# MCU_and_POWER.net
KiCad netlist of a schematic drawn in Altium Designer
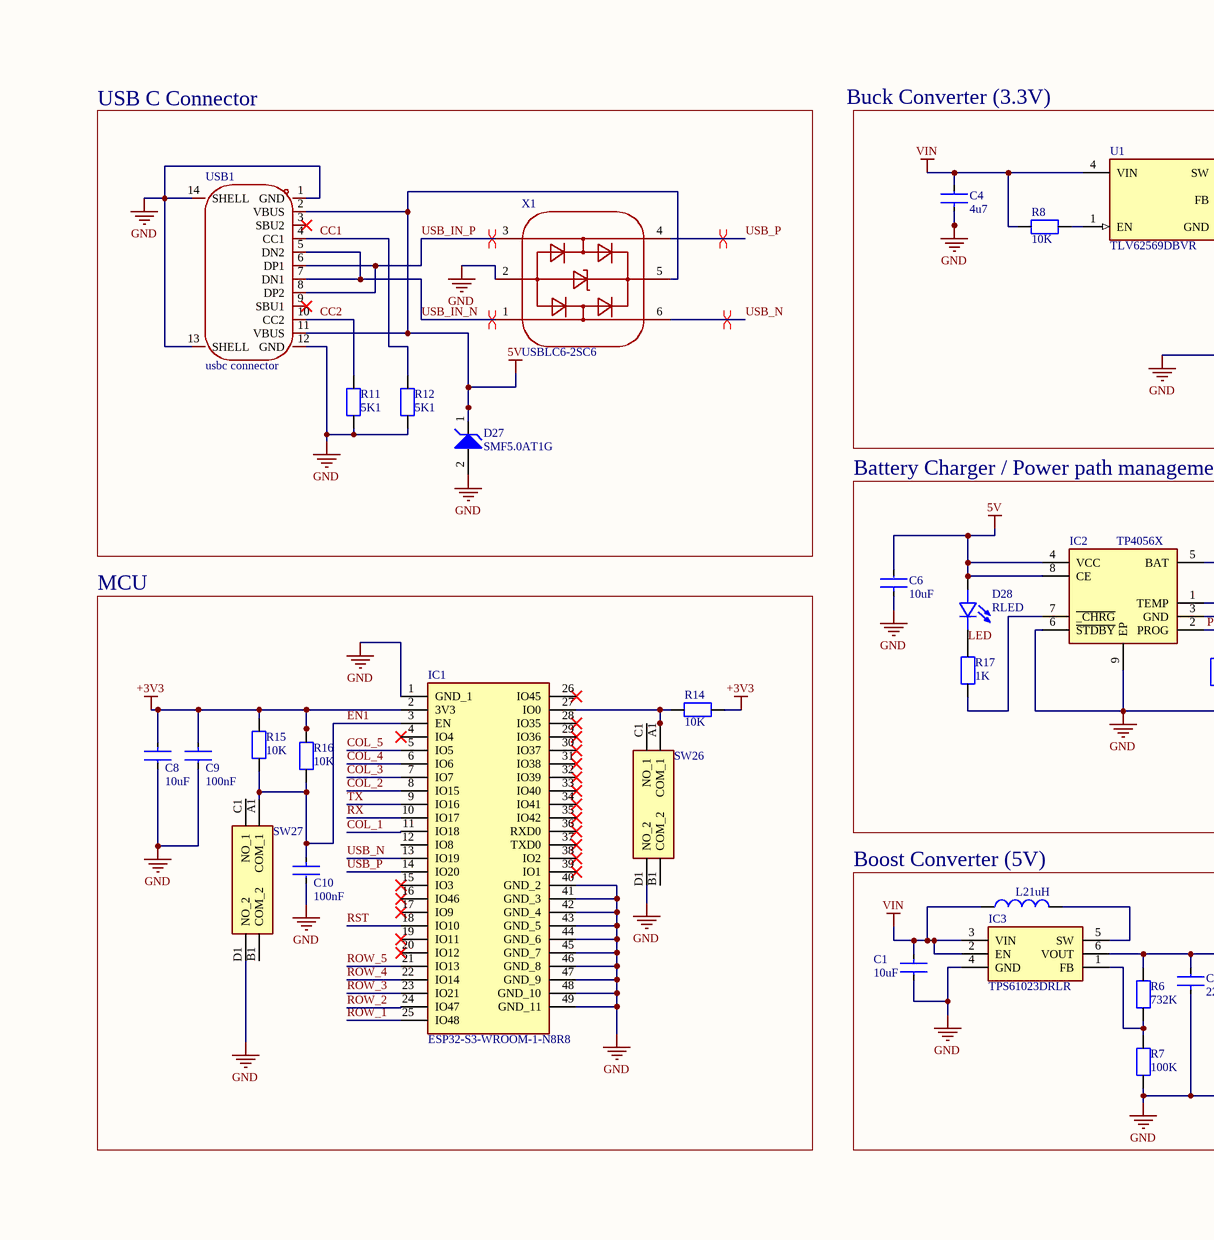
[diagram p0: MCU and POWER.SchDoc, left]
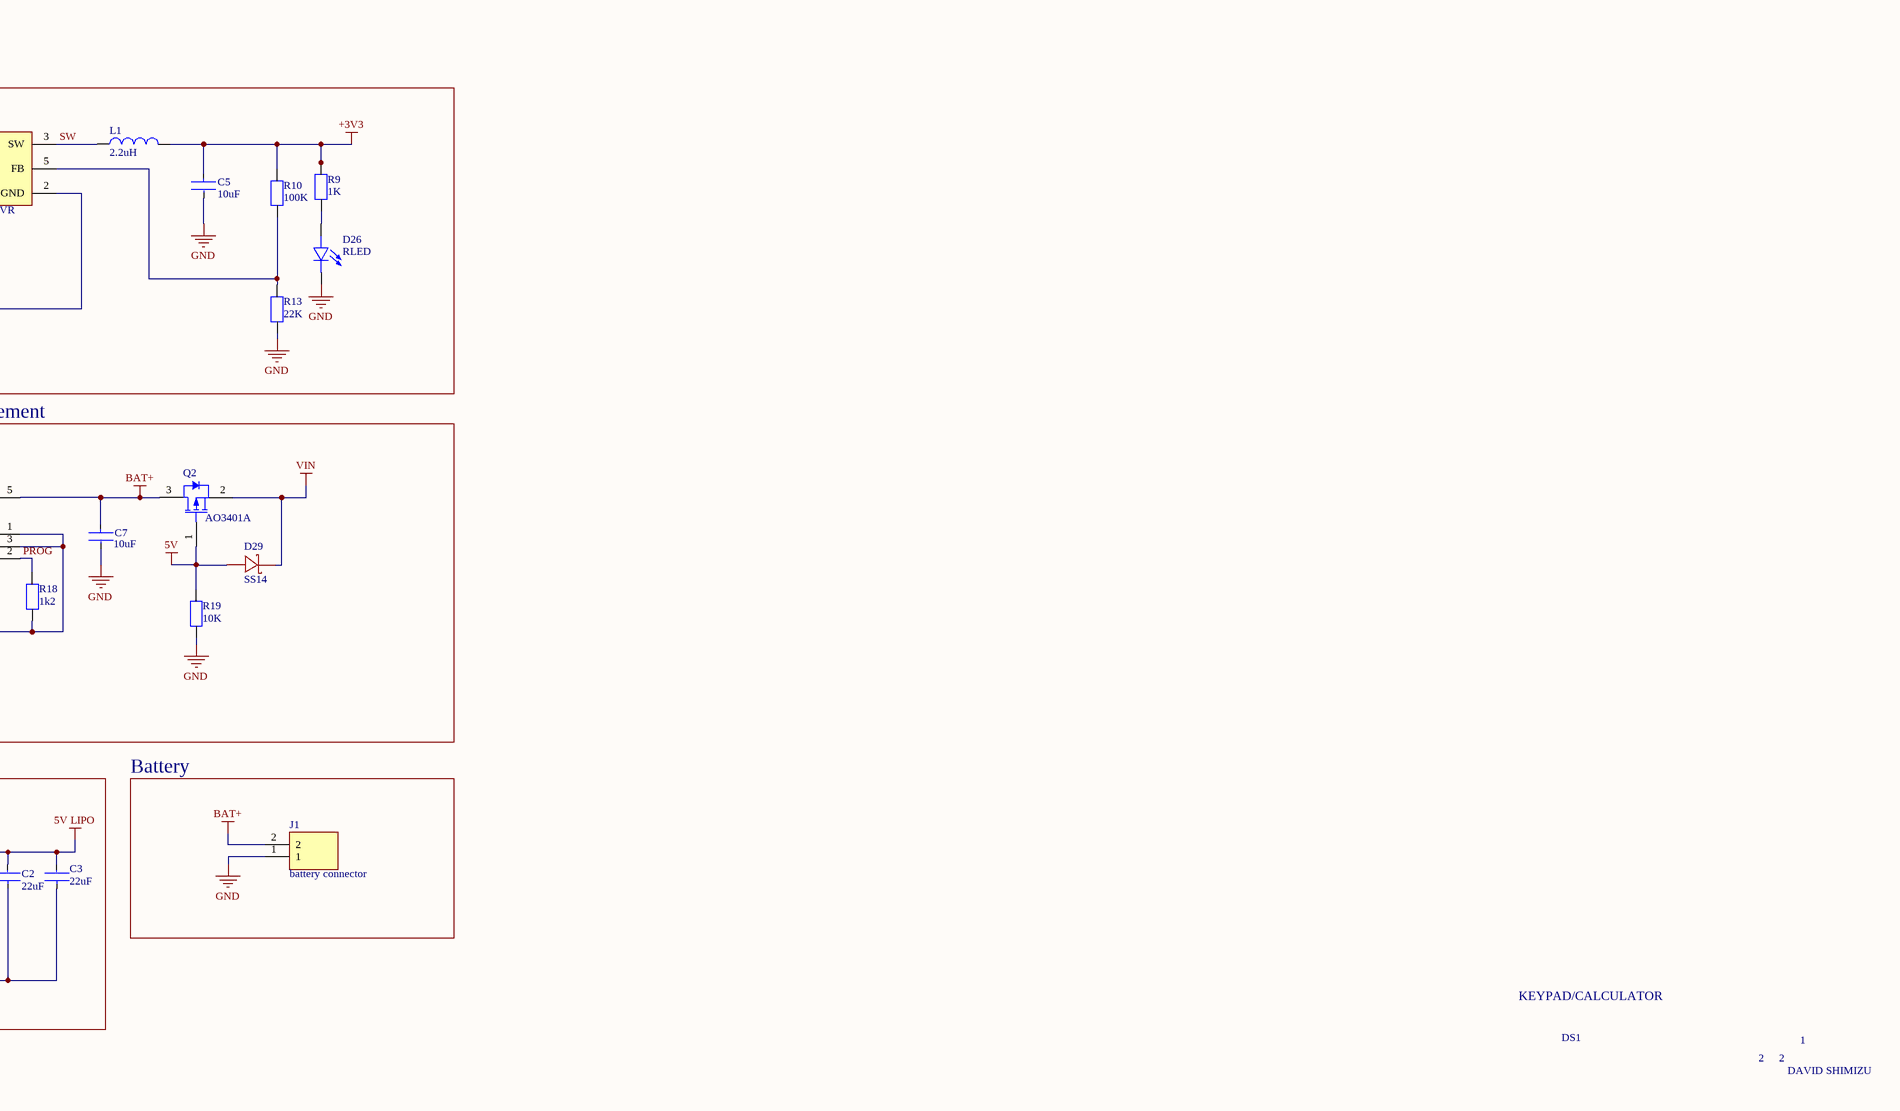
[diagram p1: MCU and POWER.SchDoc, right]

(export (version "E")
  (design (tool "Eeschema 10.0.6"))
  (components
    (comp (ref "C1")
      (value "10uF")
      (footprint "0402 capacitor")
      (description "0402 smd capacitor")
      (libsource (lib "schematiclibrary") (part "0402 capacitor"))
    )
    (comp (ref "C2")
      (value "22uF")
      (footprint "0402 capacitor")
      (description "0402 smd capacitor")
      (libsource (lib "schematiclibrary") (part "0402 capacitor"))
    )
    (comp (ref "C3")
      (value "22uF")
      (footprint "0402 capacitor")
      (description "0402 smd capacitor")
      (libsource (lib "schematiclibrary") (part "0402 capacitor"))
    )
    (comp (ref "C4")
      (value "4u7")
      (footprint "0402 capacitor")
      (description "0402 smd capacitor")
      (libsource (lib "schematiclibrary") (part "0402 capacitor"))
    )
    (comp (ref "C5")
      (value "10uF")
      (footprint "0402 capacitor")
      (description "0402 smd capacitor")
      (libsource (lib "schematiclibrary") (part "0402 capacitor"))
    )
    (comp (ref "C6")
      (value "10uF")
      (footprint "0603 CAPACITOR")
      (libsource (lib "schematiclibrary") (part "0603 capacitor"))
    )
    (comp (ref "C7")
      (value "10uF")
      (footprint "0603 CAPACITOR")
      (libsource (lib "schematiclibrary") (part "0603 capacitor"))
    )
    (comp (ref "C8")
      (value "10uF")
      (footprint "0603 CAPACITOR")
      (libsource (lib "schematiclibrary") (part "0603 capacitor"))
    )
    (comp (ref "C9")
      (value "100nF")
      (footprint "0402 capacitor")
      (description "0402 smd capacitor")
      (libsource (lib "schematiclibrary") (part "0402 capacitor"))
    )
    (comp (ref "C10")
      (value "100nF")
      (footprint "0402 capacitor")
      (description "0402 smd capacitor")
      (libsource (lib "schematiclibrary") (part "0402 capacitor"))
    )
    (comp (ref "D26")
      (value "RLED")
      (footprint "LED_KT-0603R")
      (description "Red 0603 Light Emitting Diodes")
      (fields (field (name "MF") "Hubei KENTO Elec") (field (name "MP") "KT-0603R"))
      (libsource (lib "KT-0603R") (part "KT-0603R"))
    )
    (comp (ref "D27")
      (value "SMF5.0AT1G")
      (footprint "ONSC-SOD-123FL-2-498_V")
      (description "200 W Transient Voltage Suppressor, 2-Pin SOD-123FL, Pb-Free, Tape and Reel")
      (fields (field (name "MANUFACTURER") "On Semiconductor"))
      (libsource (lib "Altium Content Vault") (part "ONSC-K1A2-2"))
    )
    (comp (ref "D28")
      (value "RLED")
      (footprint "LED_KT-0603R")
      (description "Red 0603 Light Emitting Diodes")
      (fields (field (name "MF") "Hubei KENTO Elec") (field (name "MP") "KT-0603R"))
      (libsource (lib "KT-0603R") (part "KT-0603R"))
    )
    (comp (ref "D29")
      (value "SS14")
      (footprint "SMA(DO-214AC)(schottky)")
      (description "40V Independent Type 1A 550mV@1A SMA(DO-214AC) Schottky Diodes ROHS")
      (libsource (lib "schematiclibrary") (part "ss14"))
    )
    (comp (ref "IC1")
      (value "ESP32-S3-WROOM-1-N8R8")
      (footprint "ESP32-S3-WROOM-1-N8R8")
      (libsource (lib "schematiclibrary") (part "ESP32-S3-WROOM-1-N8R8"))
    )
    (comp (ref "IC2")
      (value "TP4056X")
      (footprint "SamacSys:SOIC127P600X175-9N")
      (description "Integrated Circuit")
      (libsource (lib "SamacSys") (part "TP4056X"))
    )
    (comp (ref "IC3")
      (value "TPS61023DRLR")
      (footprint "SamacSys:SOTFL50P160X60-6N")
      (description "Integrated Circuit")
      (fields (field (name "MOUSER PART NUMBER") "595-TPS61023DRLR"))
      (libsource (lib "SamacSys") (part "TPS61023DRLR"))
    )
    (comp (ref "J1")
      (value "battery connector")
      (footprint "2pin wire to board")
      (libsource (lib "schematiclibrary") (part "2pin wire to board"))
    )
    (comp (ref "L1")
      (value "2.2uH")
      (footprint "0603 inductor")
      (libsource (lib "schematiclibrary") (part "0603 inductor"))
    )
    (comp (ref "L2")
      (value "1uH")
      (footprint "0802 inductor")
      (libsource (lib "schematiclibrary") (part "0805 inductor"))
    )
    (comp (ref "Q2")
      (value "AO3401A")
      (footprint "AO-SOT-23-3L_V")
      (description "P-Channel MOSFET, 30 V, 4 A, -55 to 150 degC, 3-Pin SOT-23-3L, RoHS, Tape and Reel")
      (fields (field (name "MANUFACTURER") "Alpha and Omega"))
      (libsource (lib "Altium Content Vault") (part "PEMOS-GSD-3"))
    )
    (comp (ref "R6")
      (value "732K")
      (footprint "0402 resistor")
      (libsource (lib "schematiclibrary") (part "0402 resistor"))
    )
    (comp (ref "R7")
      (value "100K")
      (footprint "0402 resistor")
      (libsource (lib "schematiclibrary") (part "0402 resistor"))
    )
    (comp (ref "R8")
      (value "10K")
      (footprint "0603 resistor")
      (libsource (lib "schematiclibrary") (part "0603 resistor"))
    )
    (comp (ref "R9")
      (value "1K")
      (footprint "0402 resistor")
      (libsource (lib "schematiclibrary") (part "0402 resistor"))
    )
    (comp (ref "R10")
      (value "100K")
      (footprint "0603 resistor")
      (libsource (lib "") (part "0603 resistor_1"))
    )
    (comp (ref "R11") (value "5K1") (footprint "0603 resistor") (libsource (lib "") (part "0603 resistor_1")))
    (comp (ref "R12") (value "5K1") (footprint "0603 resistor") (libsource (lib "") (part "0603 resistor_1")))
    (comp (ref "R13") (value "22K") (footprint "0603 resistor") (libsource (lib "") (part "0603 resistor_1")))
    (comp (ref "R14") (value "10K") (footprint "0603 resistor") (libsource (lib "") (part "0603 resistor_2")))
    (comp (ref "R15") (value "10K") (footprint "0603 resistor") (libsource (lib "") (part "0603 resistor_1")))
    (comp (ref "R16") (value "10K") (footprint "0603 resistor") (libsource (lib "") (part "0603 resistor_1")))
    (comp (ref "R17")
      (value "1K")
      (footprint "0402 resistor")
      (libsource (lib "schematiclibrary") (part "0402 resistor"))
    )
    (comp (ref "R18") (value "1k2") (footprint "0603 resistor") (libsource (lib "") (part "0603 resistor_1")))
    (comp (ref "R19") (value "10K") (footprint "0603 resistor") (libsource (lib "") (part "0603 resistor_1")))
    (comp (ref "SW26")
      (value "push button")
      (footprint "push button")
      (libsource (lib "schematiclibrary") (part "push button"))
    )
    (comp (ref "SW27")
      (value "push button")
      (footprint "push button")
      (libsource (lib "schematiclibrary") (part "push button"))
    )
    (comp (ref "U1")
      (value "TLV62569DBVR")
      (footprint "FP-DBV0005A-MFG")
      (description "IC REG BUCK ADJ 2A SOT23-5")
      (libsource (lib "Altium Content Vault") (part "f8671745ee5fb9a493b385c735b730b"))
    )
    (comp (ref "USB1")
      (value "usbc connector")
      (footprint "USBC connector")
      (libsource (lib "schematiclibrary") (part "usbc connector"))
    )
    (comp (ref "X1")
      (value "USBLC6-2SC6")
      (footprint "STM-SOT23-6L_V")
      (libsource (lib "schematiclibrary") (part "USBLC6-2SC6"))
    )
  )
  (nets
    (net (code "1") (name "+3V3") (class "Default")
      (node (ref "C5") (pin "1") (pinfunction "1_1") (pintype "passive"))
      (node (ref "C8") (pin "1") (pinfunction "1_1") (pintype "passive"))
      (node (ref "C9") (pin "1") (pinfunction "1_1") (pintype "passive"))
      (node (ref "IC1") (pin "2") (pinfunction "3V3_2") (pintype "passive"))
      (node (ref "L1") (pin "2") (pinfunction "2_2") (pintype "passive"))
      (node (ref "R10") (pin "2") (pinfunction "12_2") (pintype "passive"))
      (node (ref "R14") (pin "2") (pinfunction "12_2") (pintype "passive"))
      (node (ref "R15") (pin "2") (pinfunction "12_2") (pintype "passive"))
      (node (ref "R16") (pin "2") (pinfunction "12_2") (pintype "passive"))
      (node (ref "R9") (pin "2") (pinfunction "12_2") (pintype "passive"))
    )
    (net (code "2") (name "/CC1") (class "Default")
      (node (ref "R12") (pin "2") (pinfunction "12_2") (pintype "passive"))
      (node (ref "USB1") (pin "4") (pinfunction "CC1_4") (pintype "passive"))
    )
    (net (code "3") (name "/CC2") (class "Default")
      (node (ref "R11") (pin "2") (pinfunction "12_2") (pintype "passive"))
      (node (ref "USB1") (pin "10") (pinfunction "CC2_10") (pintype "passive"))
    )
    (net (code "4") (name "/COL_1") (class "Default")
      (node (ref "IC1") (pin "11") (pinfunction "IO18_11") (pintype "passive"))
    )
    (net (code "5") (name "/COL_2") (class "Default")
      (node (ref "IC1") (pin "8") (pinfunction "IO15_8") (pintype "passive"))
    )
    (net (code "6") (name "/COL_3") (class "Default")
      (node (ref "IC1") (pin "7") (pinfunction "IO7_7") (pintype "passive"))
    )
    (net (code "7") (name "/COL_4") (class "Default")
      (node (ref "IC1") (pin "6") (pinfunction "IO6_6") (pintype "passive"))
    )
    (net (code "8") (name "/COL_5") (class "Default")
      (node (ref "IC1") (pin "5") (pinfunction "IO5_5") (pintype "passive"))
    )
    (net (code "9") (name "/EN1") (class "Default")
      (node (ref "C10") (pin "1") (pinfunction "1_1") (pintype "passive"))
      (node (ref "IC1") (pin "3") (pinfunction "EN_3") (pintype "passive"))
      (node (ref "R15") (pin "1") (pinfunction "11_1") (pintype "passive"))
      (node (ref "R16") (pin "1") (pinfunction "11_1") (pintype "passive"))
      (node (ref "SW27") (pin "A1") (pinfunction "COM_1_A1") (pintype "passive"))
    )
    (net (code "10") (name "/LED") (class "Default")
      (node (ref "D28") (pin "C") (pinfunction "C_C") (pintype "passive"))
      (node (ref "R17") (pin "2") (pinfunction "12_2") (pintype "passive"))
    )
    (net (code "11") (name "/PROG") (class "Default")
      (node (ref "IC2") (pin "2") (pinfunction "PROG_2") (pintype "passive"))
      (node (ref "R18") (pin "2") (pinfunction "12_2") (pintype "passive"))
    )
    (net (code "12") (name "/ROW_1") (class "Default")
      (node (ref "IC1") (pin "25") (pinfunction "IO48_25") (pintype "passive"))
    )
    (net (code "13") (name "/ROW_2") (class "Default")
      (node (ref "IC1") (pin "24") (pinfunction "IO47_24") (pintype "passive"))
    )
    (net (code "14") (name "/ROW_3") (class "Default")
      (node (ref "IC1") (pin "23") (pinfunction "IO21_23") (pintype "passive"))
    )
    (net (code "15") (name "/ROW_4") (class "Default")
      (node (ref "IC1") (pin "22") (pinfunction "IO14_22") (pintype "passive"))
    )
    (net (code "16") (name "/ROW_5") (class "Default")
      (node (ref "IC1") (pin "21") (pinfunction "IO13_21") (pintype "passive"))
    )
    (net (code "17") (name "/RST") (class "Default")
      (node (ref "IC1") (pin "18") (pinfunction "IO10_18") (pintype "passive"))
    )
    (net (code "18") (name "/RX") (class "Default")
      (node (ref "IC1") (pin "10") (pinfunction "IO17_10") (pintype "passive"))
    )
    (net (code "19") (name "/SW") (class "Default")
      (node (ref "L1") (pin "1") (pinfunction "1_1") (pintype "passive"))
      (node (ref "U1") (pin "3") (pinfunction "SW_3") (pintype "power_in"))
    )
    (net (code "20") (name "/TX") (class "Default")
      (node (ref "IC1") (pin "9") (pinfunction "IO16_9") (pintype "passive"))
    )
    (net (code "21") (name "/USB_IN_N") (class "Default")
      (node (ref "USB1") (pin "5") (pinfunction "DN2_5") (pintype "passive"))
      (node (ref "USB1") (pin "7") (pinfunction "DN1_7") (pintype "passive"))
      (node (ref "X1") (pin "1") (pinfunction "1_1") (pintype "passive"))
    )
    (net (code "22") (name "/USB_IN_P") (class "Default")
      (node (ref "USB1") (pin "6") (pinfunction "DP1_6") (pintype "passive"))
      (node (ref "USB1") (pin "8") (pinfunction "DP2_8") (pintype "passive"))
      (node (ref "X1") (pin "3") (pinfunction "3_3") (pintype "passive"))
    )
    (net (code "23") (name "/USB_N") (class "Default")
      (node (ref "IC1") (pin "13") (pinfunction "IO19_13") (pintype "passive"))
      (node (ref "X1") (pin "6") (pinfunction "6_6") (pintype "passive"))
    )
    (net (code "24") (name "/USB_P") (class "Default")
      (node (ref "IC1") (pin "14") (pinfunction "IO20_14") (pintype "passive"))
      (node (ref "X1") (pin "4") (pinfunction "4_4") (pintype "passive"))
    )
    (net (code "25") (name "5V") (class "Default")
      (node (ref "C6") (pin "2") (pinfunction "2_2") (pintype "passive"))
      (node (ref "D27") (pin "1") (pinfunction "K_1") (pintype "passive"))
      (node (ref "D28") (pin "A") (pinfunction "A_A") (pintype "passive"))
      (node (ref "D29") (pin "2") (pinfunction "A_2") (pintype "passive"))
      (node (ref "IC2") (pin "4") (pinfunction "VCC_4") (pintype "passive"))
      (node (ref "IC2") (pin "8") (pinfunction "CE_8") (pintype "passive"))
      (node (ref "Q2") (pin "1") (pinfunction "GATE_1") (pintype "passive"))
      (node (ref "R19") (pin "2") (pinfunction "12_2") (pintype "passive"))
      (node (ref "USB1") (pin "11") (pinfunction "VBUS_11") (pintype "passive"))
      (node (ref "USB1") (pin "2") (pinfunction "VBUS_2") (pintype "passive"))
      (node (ref "X1") (pin "5") (pinfunction "5_5") (pintype "passive"))
    )
    (net (code "26") (name "5V LIPO") (class "Default")
      (node (ref "C2") (pin "2") (pinfunction "2_2") (pintype "passive"))
      (node (ref "C3") (pin "2") (pinfunction "2_2") (pintype "passive"))
      (node (ref "IC3") (pin "6") (pinfunction "VOUT_6") (pintype "passive"))
      (node (ref "R6") (pin "2") (pinfunction "12_2") (pintype "passive"))
    )
    (net (code "27") (name "BAT+") (class "Default")
      (node (ref "C7") (pin "1") (pinfunction "1_1") (pintype "passive"))
      (node (ref "IC2") (pin "5") (pinfunction "BAT_5") (pintype "passive"))
      (node (ref "J1") (pin "2") (pinfunction "2_2") (pintype "passive"))
      (node (ref "Q2") (pin "3") (pinfunction "DRAIN_3") (pintype "passive"))
    )
    (net (code "28") (name "GND") (class "Default")
      (node (ref "C1") (pin "2") (pinfunction "2_2") (pintype "passive"))
      (node (ref "C10") (pin "2") (pinfunction "2_2") (pintype "passive"))
      (node (ref "C2") (pin "1") (pinfunction "1_1") (pintype "passive"))
      (node (ref "C3") (pin "1") (pinfunction "1_1") (pintype "passive"))
      (node (ref "C4") (pin "1") (pinfunction "1_1") (pintype "passive"))
      (node (ref "C5") (pin "2") (pinfunction "2_2") (pintype "passive"))
      (node (ref "C6") (pin "1") (pinfunction "1_1") (pintype "passive"))
      (node (ref "C7") (pin "2") (pinfunction "2_2") (pintype "passive"))
      (node (ref "C8") (pin "2") (pinfunction "2_2") (pintype "passive"))
      (node (ref "C9") (pin "2") (pinfunction "2_2") (pintype "passive"))
      (node (ref "D26") (pin "C") (pinfunction "C_C") (pintype "passive"))
      (node (ref "D27") (pin "2") (pinfunction "A_2") (pintype "passive"))
      (node (ref "IC1") (pin "1") (pinfunction "GND_1_1") (pintype "passive"))
      (node (ref "IC1") (pin "40") (pinfunction "GND_2_40") (pintype "passive"))
      (node (ref "IC1") (pin "41") (pinfunction "GND_3_41") (pintype "passive"))
      (node (ref "IC1") (pin "42") (pinfunction "GND_4_42") (pintype "passive"))
      (node (ref "IC1") (pin "43") (pinfunction "GND_5_43") (pintype "passive"))
      (node (ref "IC1") (pin "44") (pinfunction "GND_6_44") (pintype "passive"))
      (node (ref "IC1") (pin "45") (pinfunction "GND_7_45") (pintype "passive"))
      (node (ref "IC1") (pin "46") (pinfunction "GND_8_46") (pintype "passive"))
      (node (ref "IC1") (pin "47") (pinfunction "GND_9_47") (pintype "passive"))
      (node (ref "IC1") (pin "48") (pinfunction "GND_10_48") (pintype "passive"))
      (node (ref "IC1") (pin "49") (pinfunction "GND_11_49") (pintype "passive"))
      (node (ref "IC2") (pin "1") (pinfunction "TEMP_1") (pintype "passive"))
      (node (ref "IC2") (pin "3") (pinfunction "GND_3") (pintype "passive"))
      (node (ref "IC2") (pin "6") (pinfunction "~{STDBY}_6") (pintype "passive"))
      (node (ref "IC2") (pin "9") (pinfunction "EP_9") (pintype "passive"))
      (node (ref "IC3") (pin "4") (pinfunction "GND_4") (pintype "passive"))
      (node (ref "J1") (pin "1") (pinfunction "1_1") (pintype "passive"))
      (node (ref "R11") (pin "1") (pinfunction "11_1") (pintype "passive"))
      (node (ref "R12") (pin "1") (pinfunction "11_1") (pintype "passive"))
      (node (ref "R13") (pin "1") (pinfunction "11_1") (pintype "passive"))
      (node (ref "R18") (pin "1") (pinfunction "11_1") (pintype "passive"))
      (node (ref "R19") (pin "1") (pinfunction "11_1") (pintype "passive"))
      (node (ref "R7") (pin "1") (pinfunction "11_1") (pintype "passive"))
      (node (ref "SW26") (pin "D1") (pinfunction "NO_2_D1") (pintype "passive"))
      (node (ref "SW27") (pin "D1") (pinfunction "NO_2_D1") (pintype "passive"))
      (node (ref "U1") (pin "2") (pinfunction "GND_2") (pintype "power_in"))
      (node (ref "USB1") (pin "1") (pinfunction "GND_1") (pintype "passive"))
      (node (ref "USB1") (pin "12") (pinfunction "GND_12") (pintype "passive"))
      (node (ref "USB1") (pin "13") (pinfunction "SHELL_13") (pintype "passive"))
      (node (ref "USB1") (pin "14") (pinfunction "SHELL_14") (pintype "passive"))
      (node (ref "X1") (pin "2") (pinfunction "2_2") (pintype "passive"))
    )
    (net (code "29") (name "Net-(IC1-IO0)") (class "Default")
      (node (ref "IC1") (pin "27") (pinfunction "IO0_27") (pintype "passive"))
      (node (ref "R14") (pin "1") (pinfunction "11_1") (pintype "passive"))
      (node (ref "SW26") (pin "A1") (pinfunction "COM_1_A1") (pintype "passive"))
    )
    (net (code "30") (name "Net-(IC2-~{_CHRG})") (class "Default")
      (node (ref "IC2") (pin "7") (pinfunction "~{_CHRG}_7") (pintype "passive"))
      (node (ref "R17") (pin "1") (pinfunction "11_1") (pintype "passive"))
    )
    (net (code "31") (name "Net-(IC3-FB)") (class "Default")
      (node (ref "IC3") (pin "1") (pinfunction "FB_1") (pintype "passive"))
      (node (ref "R6") (pin "1") (pinfunction "11_1") (pintype "passive"))
      (node (ref "R7") (pin "2") (pinfunction "12_2") (pintype "passive"))
    )
    (net (code "32") (name "Net-(IC3-SW)") (class "Default")
      (node (ref "IC3") (pin "5") (pinfunction "SW_5") (pintype "passive"))
      (node (ref "L2") (pin "2") (pinfunction "2_2") (pintype "passive"))
    )
    (net (code "33") (name "Net-(R8-11)") (class "Default")
      (node (ref "R8") (pin "1") (pinfunction "11_1") (pintype "passive"))
      (node (ref "U1") (pin "1") (pinfunction "EN_1") (pintype "input"))
    )
    (net (code "34") (name "Net-(R9-11)") (class "Default")
      (node (ref "D26") (pin "A") (pinfunction "A_A") (pintype "passive"))
      (node (ref "R9") (pin "1") (pinfunction "11_1") (pintype "passive"))
    )
    (net (code "35") (name "Net-(R10-11)") (class "Default")
      (node (ref "R10") (pin "1") (pinfunction "11_1") (pintype "passive"))
      (node (ref "R13") (pin "2") (pinfunction "12_2") (pintype "passive"))
      (node (ref "U1") (pin "5") (pinfunction "FB_5") (pintype "passive"))
    )
    (net (code "36") (name "VIN") (class "Default")
      (node (ref "C1") (pin "1") (pinfunction "1_1") (pintype "passive"))
      (node (ref "C4") (pin "2") (pinfunction "2_2") (pintype "passive"))
      (node (ref "D29") (pin "1") (pinfunction "K_1") (pintype "passive"))
      (node (ref "IC3") (pin "2") (pinfunction "EN_2") (pintype "passive"))
      (node (ref "IC3") (pin "3") (pinfunction "VIN_3") (pintype "passive"))
      (node (ref "L2") (pin "1") (pinfunction "1_1") (pintype "passive"))
      (node (ref "Q2") (pin "2") (pinfunction "SOURCE_2") (pintype "passive"))
      (node (ref "R8") (pin "2") (pinfunction "12_2") (pintype "passive"))
      (node (ref "U1") (pin "4") (pinfunction "VIN_4") (pintype "power_in"))
    )
    (net (code "37") (name "unconnected-(IC1-IO1-Pad39)") (class "Default")
      (node (ref "IC1") (pin "39") (pinfunction "IO1_39") (pintype "passive+no_connect"))
    )
    (net (code "38") (name "unconnected-(IC1-IO2-Pad38)") (class "Default")
      (node (ref "IC1") (pin "38") (pinfunction "IO2_38") (pintype "passive+no_connect"))
    )
    (net (code "39") (name "unconnected-(IC1-IO3-Pad15)") (class "Default")
      (node (ref "IC1") (pin "15") (pinfunction "IO3_15") (pintype "passive+no_connect"))
    )
    (net (code "40") (name "unconnected-(IC1-IO4-Pad4)") (class "Default")
      (node (ref "IC1") (pin "4") (pinfunction "IO4_4") (pintype "passive+no_connect"))
    )
    (net (code "41") (name "unconnected-(IC1-IO8-Pad12)") (class "Default")
      (node (ref "IC1") (pin "12") (pinfunction "IO8_12") (pintype "passive"))
    )
    (net (code "42") (name "unconnected-(IC1-IO9-Pad17)") (class "Default")
      (node (ref "IC1") (pin "17") (pinfunction "IO9_17") (pintype "passive+no_connect"))
    )
    (net (code "43") (name "unconnected-(IC1-IO11-Pad19)") (class "Default")
      (node (ref "IC1") (pin "19") (pinfunction "IO11_19") (pintype "passive+no_connect"))
    )
    (net (code "44") (name "unconnected-(IC1-IO12-Pad20)") (class "Default")
      (node (ref "IC1") (pin "20") (pinfunction "IO12_20") (pintype "passive+no_connect"))
    )
    (net (code "45") (name "unconnected-(IC1-IO35-Pad28)") (class "Default")
      (node (ref "IC1") (pin "28") (pinfunction "IO35_28") (pintype "passive+no_connect"))
    )
    (net (code "46") (name "unconnected-(IC1-IO36-Pad29)") (class "Default")
      (node (ref "IC1") (pin "29") (pinfunction "IO36_29") (pintype "passive+no_connect"))
    )
    (net (code "47") (name "unconnected-(IC1-IO37-Pad30)") (class "Default")
      (node (ref "IC1") (pin "30") (pinfunction "IO37_30") (pintype "passive+no_connect"))
    )
    (net (code "48") (name "unconnected-(IC1-IO38-Pad31)") (class "Default")
      (node (ref "IC1") (pin "31") (pinfunction "IO38_31") (pintype "passive+no_connect"))
    )
    (net (code "49") (name "unconnected-(IC1-IO39-Pad32)") (class "Default")
      (node (ref "IC1") (pin "32") (pinfunction "IO39_32") (pintype "passive+no_connect"))
    )
    (net (code "50") (name "unconnected-(IC1-IO40-Pad33)") (class "Default")
      (node (ref "IC1") (pin "33") (pinfunction "IO40_33") (pintype "passive+no_connect"))
    )
    (net (code "51") (name "unconnected-(IC1-IO41-Pad34)") (class "Default")
      (node (ref "IC1") (pin "34") (pinfunction "IO41_34") (pintype "passive+no_connect"))
    )
    (net (code "52") (name "unconnected-(IC1-IO42-Pad35)") (class "Default")
      (node (ref "IC1") (pin "35") (pinfunction "IO42_35") (pintype "passive+no_connect"))
    )
    (net (code "53") (name "unconnected-(IC1-IO45-Pad26)") (class "Default")
      (node (ref "IC1") (pin "26") (pinfunction "IO45_26") (pintype "passive+no_connect"))
    )
    (net (code "54") (name "unconnected-(IC1-IO46-Pad16)") (class "Default")
      (node (ref "IC1") (pin "16") (pinfunction "IO46_16") (pintype "passive+no_connect"))
    )
    (net (code "55") (name "unconnected-(IC1-RXD0-Pad36)") (class "Default")
      (node (ref "IC1") (pin "36") (pinfunction "RXD0_36") (pintype "passive+no_connect"))
    )
    (net (code "56") (name "unconnected-(IC1-TXD0-Pad37)") (class "Default")
      (node (ref "IC1") (pin "37") (pinfunction "TXD0_37") (pintype "passive+no_connect"))
    )
    (net (code "57") (name "unconnected-(SW26-COM_2-PadB1)") (class "Default")
      (node (ref "SW26") (pin "B1") (pinfunction "COM_2_B1") (pintype "passive"))
    )
    (net (code "58") (name "unconnected-(SW26-NO_1-PadC1)") (class "Default")
      (node (ref "SW26") (pin "C1") (pinfunction "NO_1_C1") (pintype "passive"))
    )
    (net (code "59") (name "unconnected-(SW27-COM_2-PadB1)") (class "Default")
      (node (ref "SW27") (pin "B1") (pinfunction "COM_2_B1") (pintype "passive"))
    )
    (net (code "60") (name "unconnected-(SW27-NO_1-PadC1)") (class "Default")
      (node (ref "SW27") (pin "C1") (pinfunction "NO_1_C1") (pintype "passive"))
    )
    (net (code "61") (name "unconnected-(USB1-SBU1-Pad9)") (class "Default")
      (node (ref "USB1") (pin "9") (pinfunction "SBU1_9") (pintype "passive+no_connect"))
    )
    (net (code "62") (name "unconnected-(USB1-SBU2-Pad3)") (class "Default")
      (node (ref "USB1") (pin "3") (pinfunction "SBU2_3") (pintype "passive+no_connect"))
    )
  )
)
